# vehicle_control_module_0_1_0.net
KiCad netlist of a schematic drawn in EAGLE
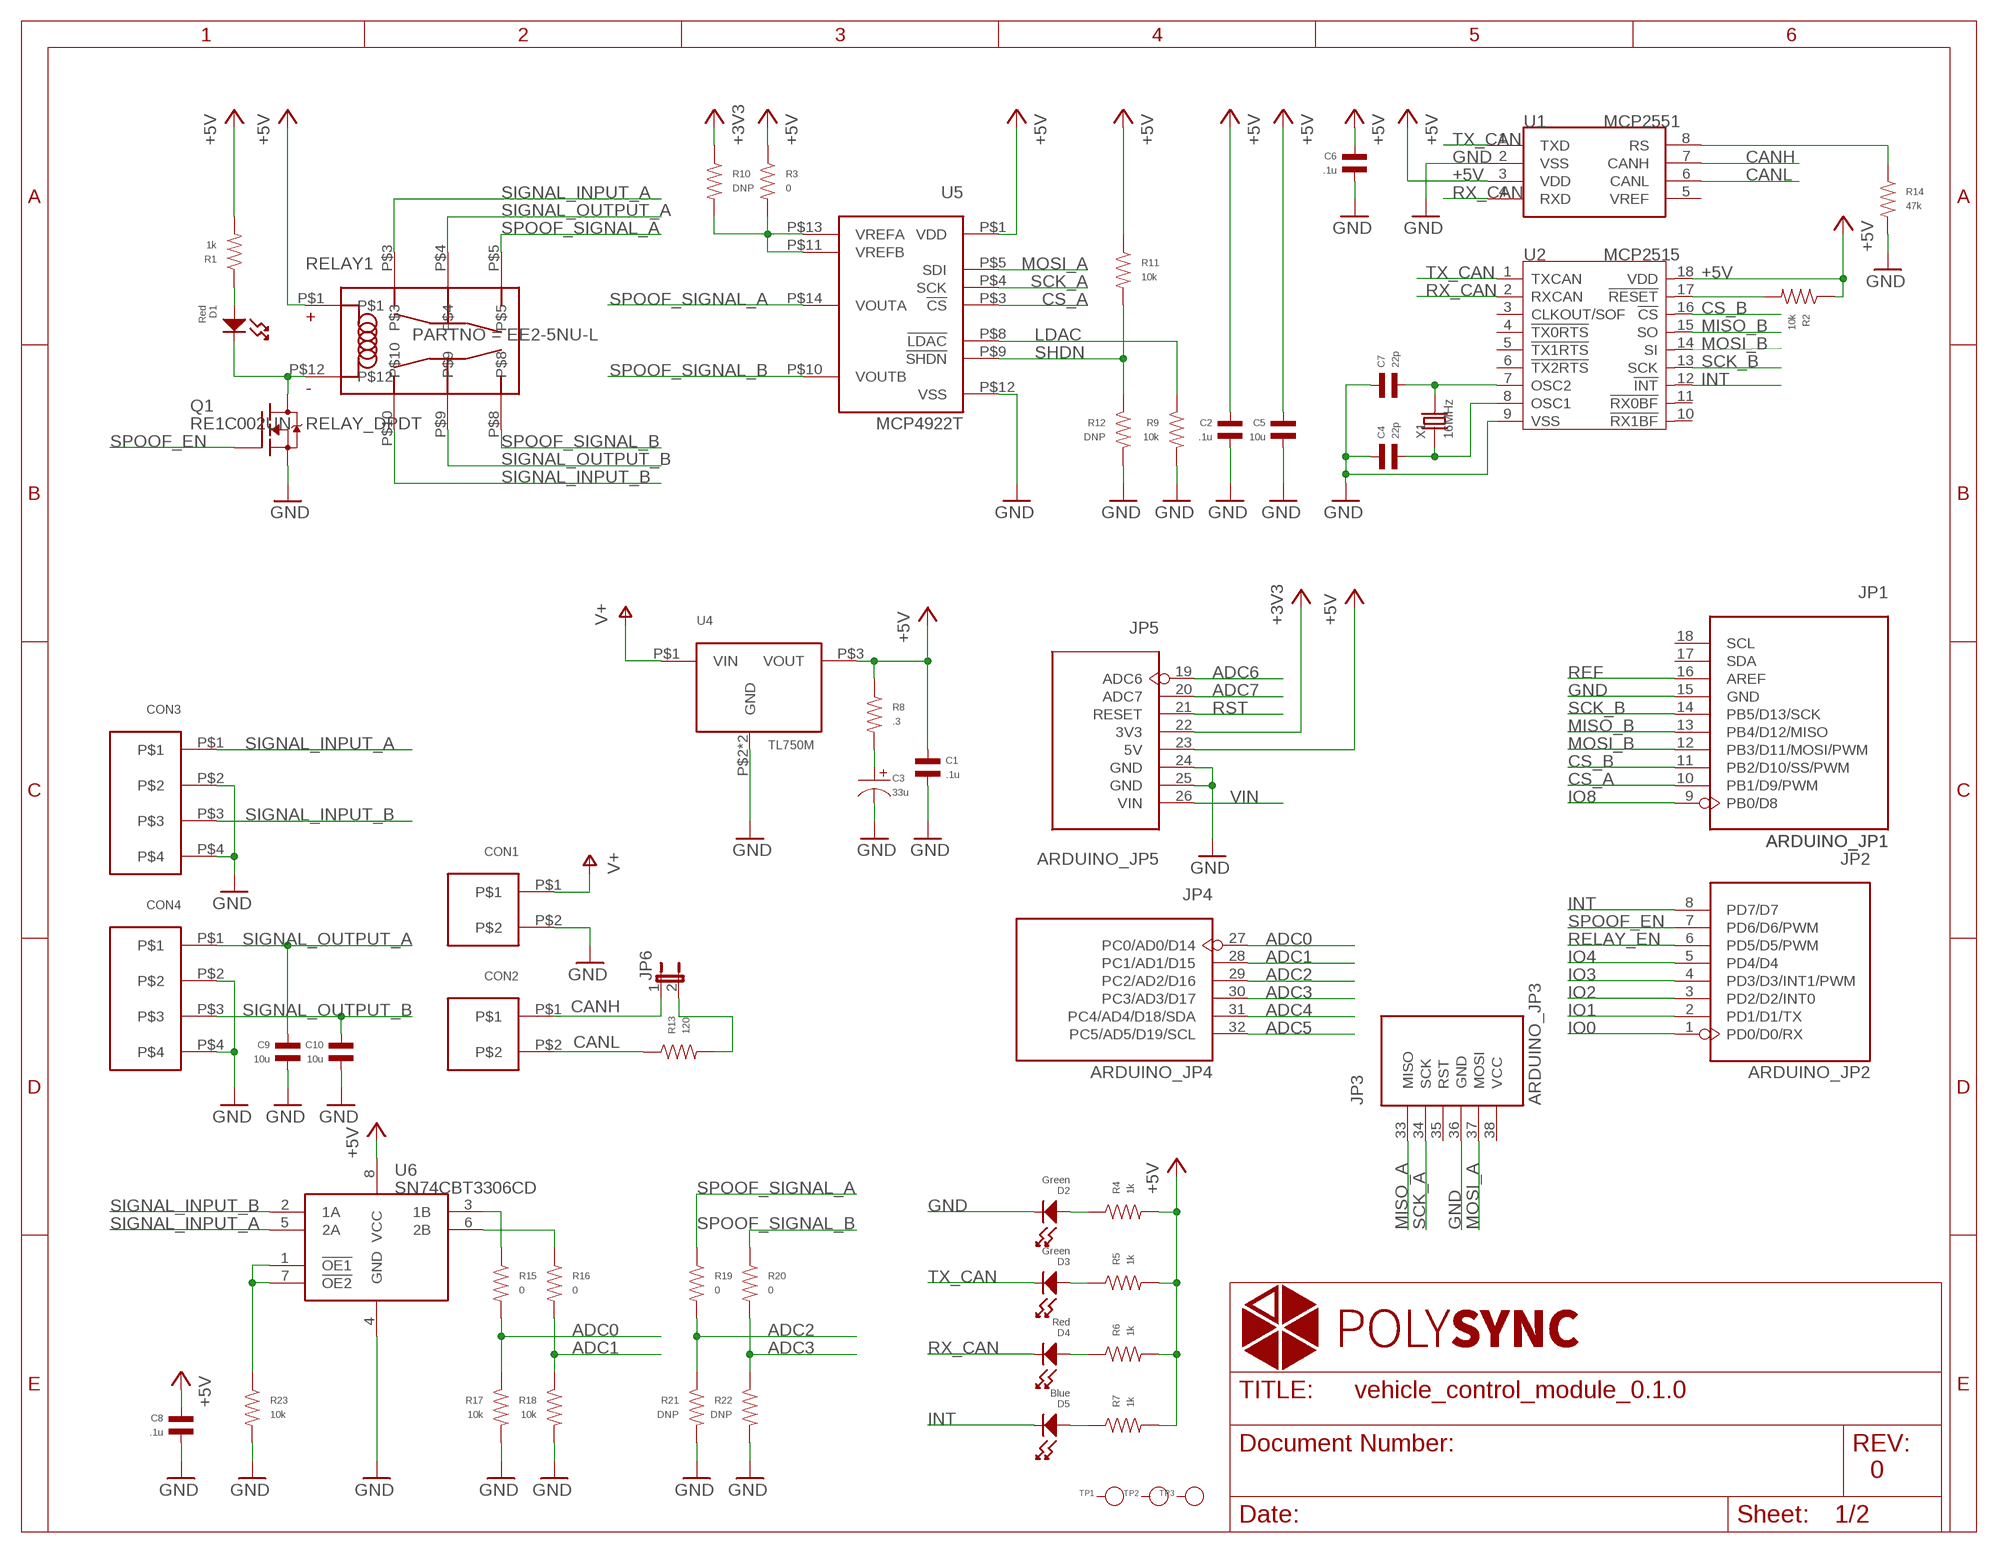
[diagram p0: schematic, sheet 1]
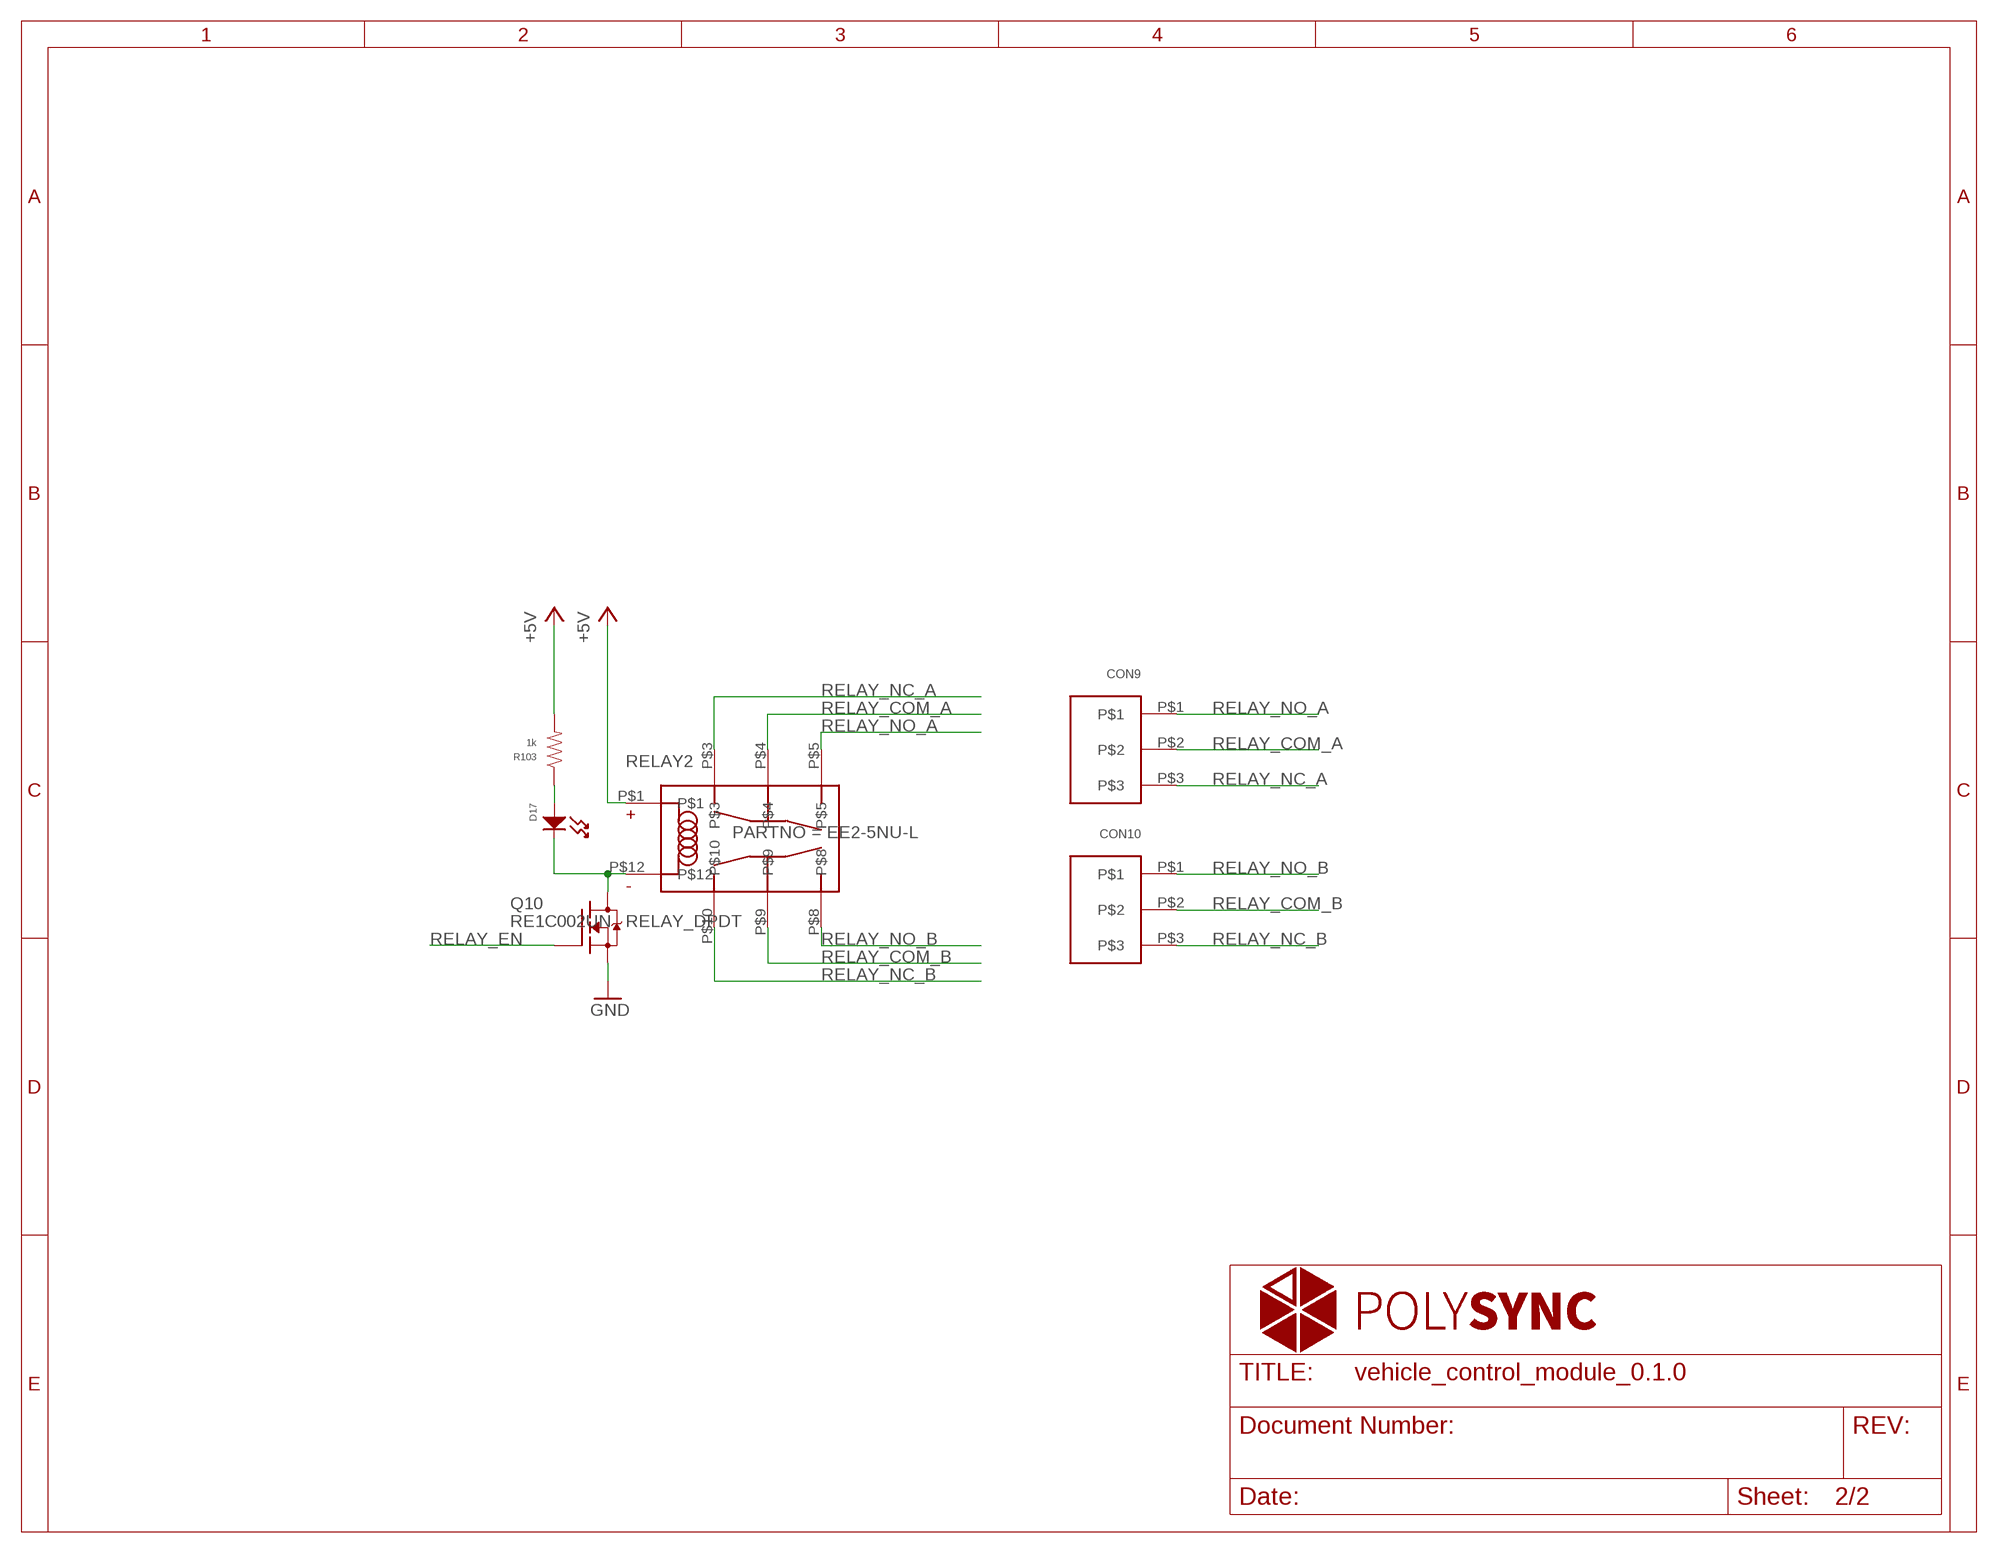
[diagram p1: schematic, sheet 2]

(export (version "E")
  (design (tool "Eeschema 10.0.6"))
  (components
    (comp (ref "CON9")
      (value "CON3")
      (footprint "eagle-import:PHOENIX_3_45")
      (libsource (lib "eagle-import") (part "CON3"))
    )
    (comp (ref "CON10")
      (value "CON3")
      (footprint "eagle-import:PHOENIX_3_45")
      (libsource (lib "eagle-import") (part "CON3"))
    )
    (comp (ref "D17")
      (value "LED_SINGLE-0603")
      (footprint "eagle-import:LED0603")
      (fields (field (name "HOUSEPART") "NO"))
      (libsource (lib "eagle-import") (part "LED_SINGLE-0603"))
    )
    (comp (ref "Q10")
      (value "RE1C002UN")
      (footprint "eagle-import:EMT3F")
      (libsource (lib "eagle-import") (part "RE1C002UN"))
    )
    (comp (ref "R103")
      (value "1k")
      (footprint "eagle-import:R0402")
      (libsource (lib "eagle-import") (part "RESISTOR_0402"))
    )
    (comp (ref "RELAY2")
      (value "RELAY_DPDT")
      (footprint "eagle-import:KEMET_EE2")
      (fields (field (name "PARTNO") "EE2-5NU-L"))
      (libsource (lib "eagle-import") (part "RELAY_DPDT"))
    )
    (comp (ref "C1")
      (value ".1u")
      (footprint "eagle-import:C0402")
      (libsource (lib "eagle-import") (part "CAPACITOR_NP_0402"))
    )
    (comp (ref "C2")
      (value ".1u")
      (footprint "eagle-import:C0402")
      (libsource (lib "eagle-import") (part "CAPACITOR_NP_0402"))
    )
    (comp (ref "C3")
      (value "33u")
      (footprint "eagle-import:CP1206")
      (libsource (lib "eagle-import") (part "CAPACITOR_P"))
    )
    (comp (ref "C4")
      (value "22p")
      (footprint "eagle-import:C0402")
      (libsource (lib "eagle-import") (part "CAPACITOR_NP_0402"))
    )
    (comp (ref "C5")
      (value "10u")
      (footprint "eagle-import:C0805")
      (libsource (lib "eagle-import") (part "CAPACITOR_NP_0805"))
    )
    (comp (ref "C6")
      (value ".1u")
      (footprint "eagle-import:C0402")
      (libsource (lib "eagle-import") (part "CAPACITOR_NP_0402"))
    )
    (comp (ref "C7")
      (value "22p")
      (footprint "eagle-import:C0402")
      (libsource (lib "eagle-import") (part "CAPACITOR_NP_0402"))
    )
    (comp (ref "C8")
      (value ".1u")
      (footprint "eagle-import:C0402")
      (libsource (lib "eagle-import") (part "CAPACITOR_NP_0402"))
    )
    (comp (ref "C9")
      (value "10u")
      (footprint "eagle-import:C0805")
      (libsource (lib "eagle-import") (part "CAPACITOR_NP_0805"))
    )
    (comp (ref "C10")
      (value "10u")
      (footprint "eagle-import:C0805")
      (libsource (lib "eagle-import") (part "CAPACITOR_NP_0805"))
    )
    (comp (ref "CON1")
      (value "CON23.5MM")
      (footprint "eagle-import:PHOENIX_2_45")
      (libsource (lib "eagle-import") (part "CON23.5MM"))
    )
    (comp (ref "CON2")
      (value "CON23.5MM")
      (footprint "eagle-import:PHOENIX_2_45")
      (libsource (lib "eagle-import") (part "CON23.5MM"))
    )
    (comp (ref "CON3")
      (value "CON4")
      (footprint "eagle-import:PHOENIX_4_45")
      (libsource (lib "eagle-import") (part "CON4"))
    )
    (comp (ref "CON4")
      (value "CON4")
      (footprint "eagle-import:PHOENIX_4_45")
      (libsource (lib "eagle-import") (part "CON4"))
    )
    (comp (ref "D1")
      (value "Red")
      (footprint "eagle-import:LED0603")
      (fields (field (name "HOUSEPART") "NO"))
      (libsource (lib "eagle-import") (part "LED_SINGLE-0603"))
    )
    (comp (ref "D2")
      (value "Green")
      (footprint "eagle-import:LED0603")
      (fields (field (name "HOUSEPART") "NO"))
      (libsource (lib "eagle-import") (part "LED_SINGLE-0603"))
    )
    (comp (ref "D3")
      (value "Green")
      (footprint "eagle-import:LED0603")
      (fields (field (name "HOUSEPART") "NO"))
      (libsource (lib "eagle-import") (part "LED_SINGLE-0603"))
    )
    (comp (ref "D4")
      (value "Red")
      (footprint "eagle-import:LED0603")
      (fields (field (name "HOUSEPART") "NO"))
      (libsource (lib "eagle-import") (part "LED_SINGLE-0603"))
    )
    (comp (ref "D5")
      (value "Blue")
      (footprint "eagle-import:LED0603")
      (fields (field (name "HOUSEPART") "NO"))
      (libsource (lib "eagle-import") (part "LED_SINGLE-0603"))
    )
    (comp (ref "JP1")
      (value "ARDUINO_JP1")
      (footprint "eagle-import:ARDUINO_JP1")
      (libsource (lib "eagle-import") (part "ARDUINO_JP1"))
    )
    (comp (ref "JP2")
      (value "ARDUINO_JP2")
      (footprint "eagle-import:ARDUINO_JP2")
      (libsource (lib "eagle-import") (part "ARDUINO_JP2"))
    )
    (comp (ref "JP3")
      (value "ARDUINO_JP3")
      (footprint "eagle-import:ARDUINO_JP3")
      (libsource (lib "eagle-import") (part "ARDUINO_JP3"))
    )
    (comp (ref "JP4")
      (value "ARDUINO_JP4")
      (footprint "eagle-import:ARDUINO_JP4")
      (libsource (lib "eagle-import") (part "ARDUINO_JP4"))
    )
    (comp (ref "JP5")
      (value "ARDUINO_JP5")
      (footprint "eagle-import:ARDUINO_JP5")
      (libsource (lib "eagle-import") (part "ARDUINO_JP5"))
    )
    (comp (ref "JP6")
      (value "JP1E")
      (footprint "eagle-import:JP1")
      (libsource (lib "eagle-import") (part "JP1E"))
    )
    (comp (ref "Q1")
      (value "RE1C002UN")
      (footprint "eagle-import:EMT3F")
      (libsource (lib "eagle-import") (part "RE1C002UN"))
    )
    (comp (ref "R1")
      (value "1k")
      (footprint "eagle-import:R0402")
      (libsource (lib "eagle-import") (part "RESISTOR_0402"))
    )
    (comp (ref "R2")
      (value "10k")
      (footprint "eagle-import:R0402")
      (libsource (lib "eagle-import") (part "RESISTOR_0402"))
    )
    (comp (ref "R3")
      (value "0")
      (footprint "eagle-import:R0402")
      (libsource (lib "eagle-import") (part "RESISTOR_0402"))
    )
    (comp (ref "R4")
      (value "1k")
      (footprint "eagle-import:R0402")
      (libsource (lib "eagle-import") (part "RESISTOR_0402"))
    )
    (comp (ref "R5")
      (value "1k")
      (footprint "eagle-import:R0402")
      (libsource (lib "eagle-import") (part "RESISTOR_0402"))
    )
    (comp (ref "R6")
      (value "1k")
      (footprint "eagle-import:R0402")
      (libsource (lib "eagle-import") (part "RESISTOR_0402"))
    )
    (comp (ref "R7")
      (value "1k")
      (footprint "eagle-import:R0402")
      (libsource (lib "eagle-import") (part "RESISTOR_0402"))
    )
    (comp (ref "R8")
      (value ".3")
      (footprint "eagle-import:R0402")
      (libsource (lib "eagle-import") (part "RESISTOR_0402"))
    )
    (comp (ref "R9")
      (value "10k")
      (footprint "eagle-import:R0402")
      (libsource (lib "eagle-import") (part "RESISTOR_0402"))
    )
    (comp (ref "R10")
      (value "DNP")
      (footprint "eagle-import:R0402")
      (libsource (lib "eagle-import") (part "RESISTOR_0402"))
    )
    (comp (ref "R11")
      (value "10k")
      (footprint "eagle-import:R0402")
      (libsource (lib "eagle-import") (part "RESISTOR_0402"))
    )
    (comp (ref "R12")
      (value "DNP")
      (footprint "eagle-import:R0402")
      (libsource (lib "eagle-import") (part "RESISTOR_0402"))
    )
    (comp (ref "R13")
      (value "120")
      (footprint "eagle-import:R0402")
      (libsource (lib "eagle-import") (part "RESISTOR_0402"))
    )
    (comp (ref "R14")
      (value "47k")
      (footprint "eagle-import:R0402")
      (libsource (lib "eagle-import") (part "RESISTOR_0402"))
    )
    (comp (ref "R15")
      (value "0")
      (footprint "eagle-import:R0402")
      (libsource (lib "eagle-import") (part "RESISTOR_0402"))
    )
    (comp (ref "R16")
      (value "0")
      (footprint "eagle-import:R0402")
      (libsource (lib "eagle-import") (part "RESISTOR_0402"))
    )
    (comp (ref "R17")
      (value "10k")
      (footprint "eagle-import:R0402")
      (libsource (lib "eagle-import") (part "RESISTOR_0402"))
    )
    (comp (ref "R18")
      (value "10k")
      (footprint "eagle-import:R0402")
      (libsource (lib "eagle-import") (part "RESISTOR_0402"))
    )
    (comp (ref "R19")
      (value "0")
      (footprint "eagle-import:R0402")
      (libsource (lib "eagle-import") (part "RESISTOR_0402"))
    )
    (comp (ref "R20")
      (value "0")
      (footprint "eagle-import:R0402")
      (libsource (lib "eagle-import") (part "RESISTOR_0402"))
    )
    (comp (ref "R21")
      (value "DNP")
      (footprint "eagle-import:R0402")
      (libsource (lib "eagle-import") (part "RESISTOR_0402"))
    )
    (comp (ref "R22")
      (value "DNP")
      (footprint "eagle-import:R0402")
      (libsource (lib "eagle-import") (part "RESISTOR_0402"))
    )
    (comp (ref "R23")
      (value "10k")
      (footprint "eagle-import:R0402")
      (libsource (lib "eagle-import") (part "RESISTOR_0402"))
    )
    (comp (ref "RELAY1")
      (value "RELAY_DPDT")
      (footprint "eagle-import:KEMET_EE2")
      (fields (field (name "PARTNO") "EE2-5NU-L"))
      (libsource (lib "eagle-import") (part "RELAY_DPDT"))
    )
    (comp (ref "TP1")
      (value "PAD-TEST-POINT'4545'")
      (footprint "eagle-import:TP_4545")
      (fields (field (name "PARTNO") "DNP"))
      (libsource (lib "eagle-import") (part "PAD-TEST-POINT'4545'"))
    )
    (comp (ref "TP2")
      (value "PAD-TEST-POINT'4545'")
      (footprint "eagle-import:TP_4545")
      (fields (field (name "PARTNO") "DNP"))
      (libsource (lib "eagle-import") (part "PAD-TEST-POINT'4545'"))
    )
    (comp (ref "TP3")
      (value "PAD-TEST-POINT'4545'")
      (footprint "eagle-import:TP_4545")
      (fields (field (name "PARTNO") "DNP"))
      (libsource (lib "eagle-import") (part "PAD-TEST-POINT'4545'"))
    )
    (comp (ref "U1")
      (value "MCP2551")
      (footprint "eagle-import:SOIC8-6.0")
      (libsource (lib "eagle-import") (part "MCP2551-SOIC8"))
    )
    (comp (ref "U2")
      (value "MCP2515")
      (footprint "eagle-import:SOIC18")
      (libsource (lib "eagle-import") (part "MCP2515-SOIC18"))
    )
    (comp (ref "U4")
      (value "TL750M")
      (footprint "eagle-import:TO-263")
      (libsource (lib "eagle-import") (part "TL750M"))
    )
    (comp (ref "U5")
      (value "MCP4922T")
      (footprint "eagle-import:TSSOP-14")
      (libsource (lib "eagle-import") (part "MCP4922T"))
    )
    (comp (ref "U6")
      (value "SN74CBT3306CD")
      (footprint "eagle-import:SOIC-8")
      (libsource (lib "eagle-import") (part "SN74CBT3306CD"))
    )
    (comp (ref "X1")
      (value "16MHz")
      (footprint "eagle-import:HC49UP")
      (libsource (lib "eagle-import") (part "CRYSTAL-HC49UP"))
    )
  )
  (nets
    (net (code "1") (name "+3V3") (class "Default")
      (node (ref "JP5") (pin "22") (pinfunction "3V3_22") (pintype "bidirectional"))
      (node (ref "R10") (pin "P$1") (pinfunction "P$1_P$1") (pintype "passive"))
    )
    (net (code "2") (name "+5V") (class "Default")
      (node (ref "C1") (pin "P$1") (pinfunction "P$1_P$1") (pintype "passive"))
      (node (ref "C2") (pin "P$1") (pinfunction "P$1_P$1") (pintype "passive"))
      (node (ref "C5") (pin "P$1") (pinfunction "P$1_P$1") (pintype "passive"))
      (node (ref "C6") (pin "P$1") (pinfunction "P$1_P$1") (pintype "passive"))
      (node (ref "C8") (pin "P$1") (pinfunction "P$1_P$1") (pintype "passive"))
      (node (ref "JP5") (pin "23") (pinfunction "5V_23") (pintype "bidirectional"))
      (node (ref "R1") (pin "P$2") (pinfunction "P$2_P$2") (pintype "passive"))
      (node (ref "R103") (pin "P$2") (pinfunction "P$2_P$2") (pintype "passive"))
      (node (ref "R11") (pin "P$1") (pinfunction "P$1_P$1") (pintype "passive"))
      (node (ref "R2") (pin "P$1") (pinfunction "P$1_P$1") (pintype "passive"))
      (node (ref "R3") (pin "P$1") (pinfunction "P$1_P$1") (pintype "passive"))
      (node (ref "R4") (pin "P$2") (pinfunction "P$2_P$2") (pintype "passive"))
      (node (ref "R5") (pin "P$2") (pinfunction "P$2_P$2") (pintype "passive"))
      (node (ref "R6") (pin "P$2") (pinfunction "P$2_P$2") (pintype "passive"))
      (node (ref "R7") (pin "P$2") (pinfunction "P$2_P$2") (pintype "passive"))
      (node (ref "R8") (pin "P$1") (pinfunction "P$1_P$1") (pintype "passive"))
      (node (ref "RELAY1") (pin "P$1") (pinfunction "P$1_P$1") (pintype "bidirectional"))
      (node (ref "RELAY2") (pin "P$1") (pinfunction "P$1_P$1") (pintype "bidirectional"))
      (node (ref "U1") (pin "3") (pinfunction "VDD_3") (pintype "bidirectional"))
      (node (ref "U2") (pin "18") (pinfunction "VDD_18") (pintype "power_in"))
      (node (ref "U4") (pin "P$3") (pinfunction "VOUT_P$3") (pintype "bidirectional"))
      (node (ref "U5") (pin "P$1") (pinfunction "VDD_P$1") (pintype "bidirectional"))
      (node (ref "U6") (pin "8") (pinfunction "VCC_8") (pintype "bidirectional"))
    )
    (net (code "3") (name "ADC0") (class "Default")
      (node (ref "JP4") (pin "27") (pinfunction "PC0/AD0/D14_27") (pintype "bidirectional"))
      (node (ref "R15") (pin "P$2") (pinfunction "P$2_P$2") (pintype "passive"))
      (node (ref "R17") (pin "P$1") (pinfunction "P$1_P$1") (pintype "passive"))
    )
    (net (code "4") (name "ADC1") (class "Default")
      (node (ref "JP4") (pin "28") (pinfunction "PC1/AD1/D15_28") (pintype "bidirectional"))
      (node (ref "R16") (pin "P$2") (pinfunction "P$2_P$2") (pintype "passive"))
      (node (ref "R18") (pin "P$1") (pinfunction "P$1_P$1") (pintype "passive"))
    )
    (net (code "5") (name "ADC2") (class "Default")
      (node (ref "JP4") (pin "29") (pinfunction "PC2/AD2/D16_29") (pintype "bidirectional"))
      (node (ref "R19") (pin "P$2") (pinfunction "P$2_P$2") (pintype "passive"))
      (node (ref "R21") (pin "P$1") (pinfunction "P$1_P$1") (pintype "passive"))
    )
    (net (code "6") (name "ADC3") (class "Default")
      (node (ref "JP4") (pin "30") (pinfunction "PC3/AD3/D17_30") (pintype "bidirectional"))
      (node (ref "R20") (pin "P$2") (pinfunction "P$2_P$2") (pintype "passive"))
      (node (ref "R22") (pin "P$1") (pinfunction "P$1_P$1") (pintype "passive"))
    )
    (net (code "7") (name "ADC4") (class "Default")
      (node (ref "JP4") (pin "31") (pinfunction "PC4/AD4/D18/SDA_31") (pintype "bidirectional"))
    )
    (net (code "8") (name "ADC5") (class "Default")
      (node (ref "JP4") (pin "32") (pinfunction "PC5/AD5/D19/SCL_32") (pintype "bidirectional"))
    )
    (net (code "9") (name "ADC6") (class "Default")
      (node (ref "JP5") (pin "19") (pinfunction "ADC6_19") (pintype "bidirectional"))
    )
    (net (code "10") (name "ADC7") (class "Default")
      (node (ref "JP5") (pin "20") (pinfunction "ADC7_20") (pintype "bidirectional"))
    )
    (net (code "11") (name "CANH") (class "Default")
      (node (ref "CON2") (pin "P$1") (pinfunction "P$1_P$1") (pintype "bidirectional"))
      (node (ref "JP6") (pin "1") (pinfunction "1_1") (pintype "passive"))
      (node (ref "U1") (pin "7") (pinfunction "CANH_7") (pintype "bidirectional"))
    )
    (net (code "12") (name "CANL") (class "Default")
      (node (ref "CON2") (pin "P$2") (pinfunction "P$2_P$2") (pintype "bidirectional"))
      (node (ref "R13") (pin "P$1") (pinfunction "P$1_P$1") (pintype "passive"))
      (node (ref "U1") (pin "6") (pinfunction "CANL_6") (pintype "bidirectional"))
    )
    (net (code "13") (name "CS_A") (class "Default")
      (node (ref "JP1") (pin "10") (pinfunction "PB1/D9/PWM_10") (pintype "bidirectional"))
      (node (ref "U5") (pin "P$3") (pinfunction "~{CS}_P$3") (pintype "bidirectional"))
    )
    (net (code "14") (name "CS_B") (class "Default")
      (node (ref "JP1") (pin "11") (pinfunction "PB2/D10/SS/PWM_11") (pintype "bidirectional"))
      (node (ref "U2") (pin "16") (pinfunction "~{CS}_16") (pintype "input"))
    )
    (net (code "15") (name "GND") (class "Default")
      (node (ref "C1") (pin "P$2") (pinfunction "P$2_P$2") (pintype "passive"))
      (node (ref "C10") (pin "P$2") (pinfunction "P$2_P$2") (pintype "passive"))
      (node (ref "C2") (pin "P$2") (pinfunction "P$2_P$2") (pintype "passive"))
      (node (ref "C3") (pin "P$2") (pinfunction "P$2_P$2") (pintype "passive"))
      (node (ref "C4") (pin "P$1") (pinfunction "P$1_P$1") (pintype "passive"))
      (node (ref "C5") (pin "P$2") (pinfunction "P$2_P$2") (pintype "passive"))
      (node (ref "C6") (pin "P$2") (pinfunction "P$2_P$2") (pintype "passive"))
      (node (ref "C7") (pin "P$1") (pinfunction "P$1_P$1") (pintype "passive"))
      (node (ref "C8") (pin "P$2") (pinfunction "P$2_P$2") (pintype "passive"))
      (node (ref "C9") (pin "P$2") (pinfunction "P$2_P$2") (pintype "passive"))
      (node (ref "CON1") (pin "P$2") (pinfunction "P$2_P$2") (pintype "bidirectional"))
      (node (ref "CON3") (pin "P$2") (pinfunction "P$2_P$2") (pintype "bidirectional"))
      (node (ref "CON3") (pin "P$4") (pinfunction "P$4_P$4") (pintype "bidirectional"))
      (node (ref "CON4") (pin "P$2") (pinfunction "P$2_P$2") (pintype "bidirectional"))
      (node (ref "CON4") (pin "P$4") (pinfunction "P$4_P$4") (pintype "bidirectional"))
      (node (ref "D2") (pin "CATHODE") (pinfunction "CATHODE_CATHODE") (pintype "power_in"))
      (node (ref "JP1") (pin "15") (pinfunction "GND_15") (pintype "bidirectional"))
      (node (ref "JP3") (pin "36") (pinfunction "GND_36") (pintype "bidirectional"))
      (node (ref "JP5") (pin "24") (pinfunction "GND_24") (pintype "bidirectional"))
      (node (ref "JP5") (pin "25") (pinfunction "GND_25") (pintype "bidirectional"))
      (node (ref "Q1") (pin "P$2") (pinfunction "S_P$2") (pintype "passive"))
      (node (ref "Q10") (pin "P$2") (pinfunction "S_P$2") (pintype "passive"))
      (node (ref "R12") (pin "P$2") (pinfunction "P$2_P$2") (pintype "passive"))
      (node (ref "R14") (pin "P$2") (pinfunction "P$2_P$2") (pintype "passive"))
      (node (ref "R17") (pin "P$2") (pinfunction "P$2_P$2") (pintype "passive"))
      (node (ref "R18") (pin "P$2") (pinfunction "P$2_P$2") (pintype "passive"))
      (node (ref "R21") (pin "P$2") (pinfunction "P$2_P$2") (pintype "passive"))
      (node (ref "R22") (pin "P$2") (pinfunction "P$2_P$2") (pintype "passive"))
      (node (ref "R23") (pin "P$2") (pinfunction "P$2_P$2") (pintype "passive"))
      (node (ref "R9") (pin "P$2") (pinfunction "P$2_P$2") (pintype "passive"))
      (node (ref "U1") (pin "2") (pinfunction "VSS_2") (pintype "bidirectional"))
      (node (ref "U2") (pin "9") (pinfunction "VSS_9") (pintype "power_in"))
      (node (ref "U4") (pin "P$2") (pinfunction "GND_P$2") (pintype "bidirectional"))
      (node (ref "U4") (pin "P$4") (pinfunction "GND_P$4") (pintype "bidirectional"))
      (node (ref "U5") (pin "P$12") (pinfunction "VSS_P$12") (pintype "bidirectional"))
      (node (ref "U6") (pin "4") (pinfunction "GND_4") (pintype "bidirectional"))
    )
    (net (code "16") (name "INT") (class "Default")
      (node (ref "D5") (pin "CATHODE") (pinfunction "CATHODE_CATHODE") (pintype "power_in"))
      (node (ref "JP2") (pin "8") (pinfunction "PD7/D7_8") (pintype "bidirectional"))
      (node (ref "U2") (pin "12") (pinfunction "~{INT}_12") (pintype "output"))
    )
    (net (code "17") (name "IO0") (class "Default")
      (node (ref "JP2") (pin "1") (pinfunction "PD0/D0/RX_1") (pintype "bidirectional"))
    )
    (net (code "18") (name "IO1") (class "Default")
      (node (ref "JP2") (pin "2") (pinfunction "PD1/D1/TX_2") (pintype "bidirectional"))
    )
    (net (code "19") (name "IO2") (class "Default")
      (node (ref "JP2") (pin "3") (pinfunction "PD2/D2/INT0_3") (pintype "bidirectional"))
    )
    (net (code "20") (name "IO3") (class "Default")
      (node (ref "JP2") (pin "4") (pinfunction "PD3/D3/INT1/PWM_4") (pintype "bidirectional"))
    )
    (net (code "21") (name "IO4") (class "Default")
      (node (ref "JP2") (pin "5") (pinfunction "PD4/D4_5") (pintype "bidirectional"))
    )
    (net (code "22") (name "IO8") (class "Default")
      (node (ref "JP1") (pin "9") (pinfunction "PB0/D8_9") (pintype "bidirectional"))
    )
    (net (code "23") (name "LDAC") (class "Default")
      (node (ref "R9") (pin "P$1") (pinfunction "P$1_P$1") (pintype "passive"))
      (node (ref "U5") (pin "P$8") (pinfunction "~{LDAC}_P$8") (pintype "bidirectional"))
    )
    (net (code "24") (name "MISO_A") (class "Default")
      (node (ref "JP3") (pin "33") (pinfunction "MISO_33") (pintype "bidirectional"))
    )
    (net (code "25") (name "MISO_B") (class "Default")
      (node (ref "JP1") (pin "13") (pinfunction "PB4/D12/MISO_13") (pintype "bidirectional"))
      (node (ref "U2") (pin "15") (pinfunction "SO_15") (pintype "output"))
    )
    (net (code "26") (name "MOSI_A") (class "Default")
      (node (ref "JP3") (pin "37") (pinfunction "MOSI_37") (pintype "bidirectional"))
      (node (ref "U5") (pin "P$5") (pinfunction "SDI_P$5") (pintype "bidirectional"))
    )
    (net (code "27") (name "MOSI_B") (class "Default")
      (node (ref "JP1") (pin "12") (pinfunction "PB3/D11/MOSI/PWM_12") (pintype "bidirectional"))
      (node (ref "U2") (pin "14") (pinfunction "SI_14") (pintype "input"))
    )
    (net (code "28") (name "Net-(C3-PadP$1)") (class "Default")
      (node (ref "C3") (pin "P$1") (pinfunction "P$1_P$1") (pintype "passive"))
      (node (ref "R8") (pin "P$2") (pinfunction "P$2_P$2") (pintype "passive"))
    )
    (net (code "29") (name "Net-(D1-PadANODE)") (class "Default")
      (node (ref "D1") (pin "ANODE") (pinfunction "ANODE_ANODE") (pintype "power_in"))
      (node (ref "R1") (pin "P$1") (pinfunction "P$1_P$1") (pintype "passive"))
    )
    (net (code "30") (name "Net-(D2-PadANODE)") (class "Default")
      (node (ref "D2") (pin "ANODE") (pinfunction "ANODE_ANODE") (pintype "power_in"))
      (node (ref "R4") (pin "P$1") (pinfunction "P$1_P$1") (pintype "passive"))
    )
    (net (code "31") (name "Net-(D3-PadANODE)") (class "Default")
      (node (ref "D3") (pin "ANODE") (pinfunction "ANODE_ANODE") (pintype "power_in"))
      (node (ref "R5") (pin "P$1") (pinfunction "P$1_P$1") (pintype "passive"))
    )
    (net (code "32") (name "Net-(D4-PadANODE)") (class "Default")
      (node (ref "D4") (pin "ANODE") (pinfunction "ANODE_ANODE") (pintype "power_in"))
      (node (ref "R6") (pin "P$1") (pinfunction "P$1_P$1") (pintype "passive"))
    )
    (net (code "33") (name "Net-(D5-PadANODE)") (class "Default")
      (node (ref "D5") (pin "ANODE") (pinfunction "ANODE_ANODE") (pintype "power_in"))
      (node (ref "R7") (pin "P$1") (pinfunction "P$1_P$1") (pintype "passive"))
    )
    (net (code "34") (name "Net-(D17-PadANODE)") (class "Default")
      (node (ref "D17") (pin "ANODE") (pinfunction "ANODE_ANODE") (pintype "power_in"))
      (node (ref "R103") (pin "P$1") (pinfunction "P$1_P$1") (pintype "passive"))
    )
    (net (code "35") (name "Net-(JP6-Pad2)") (class "Default")
      (node (ref "JP6") (pin "2") (pinfunction "2_2") (pintype "passive"))
      (node (ref "R13") (pin "P$2") (pinfunction "P$2_P$2") (pintype "passive"))
    )
    (net (code "36") (name "Net-(Q1-D)") (class "Default")
      (node (ref "D1") (pin "CATHODE") (pinfunction "CATHODE_CATHODE") (pintype "power_in"))
      (node (ref "Q1") (pin "P$3") (pinfunction "D_P$3") (pintype "passive"))
      (node (ref "RELAY1") (pin "P$12") (pinfunction "P$12_P$12") (pintype "bidirectional"))
    )
    (net (code "37") (name "Net-(Q10-D)") (class "Default")
      (node (ref "D17") (pin "CATHODE") (pinfunction "CATHODE_CATHODE") (pintype "power_in"))
      (node (ref "Q10") (pin "P$3") (pinfunction "D_P$3") (pintype "passive"))
      (node (ref "RELAY2") (pin "P$12") (pinfunction "P$12_P$12") (pintype "bidirectional"))
    )
    (net (code "38") (name "Net-(U1-RS)") (class "Default")
      (node (ref "R14") (pin "P$1") (pinfunction "P$1_P$1") (pintype "passive"))
      (node (ref "U1") (pin "8") (pinfunction "RS_8") (pintype "bidirectional"))
    )
    (net (code "39") (name "Net-(U2-OSC1)") (class "Default")
      (node (ref "C4") (pin "P$2") (pinfunction "P$2_P$2") (pintype "passive"))
      (node (ref "U2") (pin "8") (pinfunction "OSC1_8") (pintype "input"))
      (node (ref "X1") (pin "1") (pinfunction "1_1") (pintype "passive"))
    )
    (net (code "40") (name "Net-(U2-OSC2)") (class "Default")
      (node (ref "C7") (pin "P$2") (pinfunction "P$2_P$2") (pintype "passive"))
      (node (ref "U2") (pin "7") (pinfunction "OSC2_7") (pintype "output"))
      (node (ref "X1") (pin "2") (pinfunction "2_2") (pintype "passive"))
    )
    (net (code "41") (name "Net-(U2-~{RESET})") (class "Default")
      (node (ref "R2") (pin "P$2") (pinfunction "P$2_P$2") (pintype "passive"))
      (node (ref "U2") (pin "17") (pinfunction "~{RESET}_17") (pintype "input"))
    )
    (net (code "42") (name "Net-(U5-VREFA)") (class "Default")
      (node (ref "R10") (pin "P$2") (pinfunction "P$2_P$2") (pintype "passive"))
      (node (ref "R3") (pin "P$2") (pinfunction "P$2_P$2") (pintype "passive"))
      (node (ref "U5") (pin "P$11") (pinfunction "VREFB_P$11") (pintype "bidirectional"))
      (node (ref "U5") (pin "P$13") (pinfunction "VREFA_P$13") (pintype "bidirectional"))
    )
    (net (code "43") (name "Net-(U6-1B)") (class "Default")
      (node (ref "R15") (pin "P$1") (pinfunction "P$1_P$1") (pintype "passive"))
      (node (ref "U6") (pin "3") (pinfunction "1B_3") (pintype "bidirectional"))
    )
    (net (code "44") (name "Net-(U6-2B)") (class "Default")
      (node (ref "R16") (pin "P$1") (pinfunction "P$1_P$1") (pintype "passive"))
      (node (ref "U6") (pin "6") (pinfunction "2B_6") (pintype "bidirectional"))
    )
    (net (code "45") (name "Net-(U6-~{OE1})") (class "Default")
      (node (ref "R23") (pin "P$1") (pinfunction "P$1_P$1") (pintype "passive"))
      (node (ref "U6") (pin "1") (pinfunction "~{OE1}_1") (pintype "bidirectional"))
      (node (ref "U6") (pin "7") (pinfunction "~{OE2}_7") (pintype "bidirectional"))
    )
    (net (code "46") (name "REF") (class "Default")
      (node (ref "JP1") (pin "16") (pinfunction "AREF_16") (pintype "bidirectional"))
    )
    (net (code "47") (name "RELAY_COM_A") (class "Default")
      (node (ref "CON9") (pin "P$2") (pinfunction "P$2_P$2") (pintype "bidirectional"))
      (node (ref "RELAY2") (pin "P$4") (pinfunction "P$4_P$4") (pintype "bidirectional"))
    )
    (net (code "48") (name "RELAY_COM_B") (class "Default")
      (node (ref "CON10") (pin "P$2") (pinfunction "P$2_P$2") (pintype "bidirectional"))
      (node (ref "RELAY2") (pin "P$9") (pinfunction "P$9_P$9") (pintype "bidirectional"))
    )
    (net (code "49") (name "RELAY_EN") (class "Default")
      (node (ref "JP2") (pin "6") (pinfunction "PD5/D5/PWM_6") (pintype "bidirectional"))
      (node (ref "Q10") (pin "P$1") (pinfunction "G_P$1") (pintype "passive"))
    )
    (net (code "50") (name "RELAY_NC_A") (class "Default")
      (node (ref "CON9") (pin "P$3") (pinfunction "P$3_P$3") (pintype "bidirectional"))
      (node (ref "RELAY2") (pin "P$3") (pinfunction "P$3_P$3") (pintype "bidirectional"))
    )
    (net (code "51") (name "RELAY_NC_B") (class "Default")
      (node (ref "CON10") (pin "P$3") (pinfunction "P$3_P$3") (pintype "bidirectional"))
      (node (ref "RELAY2") (pin "P$10") (pinfunction "P$10_P$10") (pintype "bidirectional"))
    )
    (net (code "52") (name "RELAY_NO_A") (class "Default")
      (node (ref "CON9") (pin "P$1") (pinfunction "P$1_P$1") (pintype "bidirectional"))
      (node (ref "RELAY2") (pin "P$5") (pinfunction "P$5_P$5") (pintype "bidirectional"))
    )
    (net (code "53") (name "RELAY_NO_B") (class "Default")
      (node (ref "CON10") (pin "P$1") (pinfunction "P$1_P$1") (pintype "bidirectional"))
      (node (ref "RELAY2") (pin "P$8") (pinfunction "P$8_P$8") (pintype "bidirectional"))
    )
    (net (code "54") (name "RST") (class "Default")
      (node (ref "JP5") (pin "21") (pinfunction "RESET_21") (pintype "bidirectional"))
    )
    (net (code "55") (name "RX_CAN") (class "Default")
      (node (ref "D4") (pin "CATHODE") (pinfunction "CATHODE_CATHODE") (pintype "power_in"))
      (node (ref "U1") (pin "4") (pinfunction "RXD_4") (pintype "bidirectional"))
      (node (ref "U2") (pin "2") (pinfunction "RXCAN_2") (pintype "input"))
    )
    (net (code "56") (name "SCK_A") (class "Default")
      (node (ref "JP3") (pin "34") (pinfunction "SCK_34") (pintype "bidirectional"))
      (node (ref "U5") (pin "P$4") (pinfunction "SCK_P$4") (pintype "bidirectional"))
    )
    (net (code "57") (name "SCK_B") (class "Default")
      (node (ref "JP1") (pin "14") (pinfunction "PB5/D13/SCK_14") (pintype "bidirectional"))
      (node (ref "U2") (pin "13") (pinfunction "SCK_13") (pintype "input"))
    )
    (net (code "58") (name "SHDN") (class "Default")
      (node (ref "R11") (pin "P$2") (pinfunction "P$2_P$2") (pintype "passive"))
      (node (ref "R12") (pin "P$1") (pinfunction "P$1_P$1") (pintype "passive"))
      (node (ref "U5") (pin "P$9") (pinfunction "~{SHDN}_P$9") (pintype "bidirectional"))
    )
    (net (code "59") (name "SIGNAL_INPUT_A") (class "Default")
      (node (ref "CON3") (pin "P$1") (pinfunction "P$1_P$1") (pintype "bidirectional"))
      (node (ref "RELAY1") (pin "P$3") (pinfunction "P$3_P$3") (pintype "bidirectional"))
      (node (ref "U6") (pin "5") (pinfunction "2A_5") (pintype "bidirectional"))
    )
    (net (code "60") (name "SIGNAL_INPUT_B") (class "Default")
      (node (ref "CON3") (pin "P$3") (pinfunction "P$3_P$3") (pintype "bidirectional"))
      (node (ref "RELAY1") (pin "P$10") (pinfunction "P$10_P$10") (pintype "bidirectional"))
      (node (ref "U6") (pin "2") (pinfunction "1A_2") (pintype "bidirectional"))
    )
    (net (code "61") (name "SIGNAL_OUTPUT_A") (class "Default")
      (node (ref "C9") (pin "P$1") (pinfunction "P$1_P$1") (pintype "passive"))
      (node (ref "CON4") (pin "P$1") (pinfunction "P$1_P$1") (pintype "bidirectional"))
      (node (ref "RELAY1") (pin "P$4") (pinfunction "P$4_P$4") (pintype "bidirectional"))
    )
    (net (code "62") (name "SIGNAL_OUTPUT_B") (class "Default")
      (node (ref "C10") (pin "P$1") (pinfunction "P$1_P$1") (pintype "passive"))
      (node (ref "CON4") (pin "P$3") (pinfunction "P$3_P$3") (pintype "bidirectional"))
      (node (ref "RELAY1") (pin "P$9") (pinfunction "P$9_P$9") (pintype "bidirectional"))
    )
    (net (code "63") (name "SPOOF_EN") (class "Default")
      (node (ref "JP2") (pin "7") (pinfunction "PD6/D6/PWM_7") (pintype "bidirectional"))
      (node (ref "Q1") (pin "P$1") (pinfunction "G_P$1") (pintype "passive"))
    )
    (net (code "64") (name "SPOOF_SIGNAL_A") (class "Default")
      (node (ref "R19") (pin "P$1") (pinfunction "P$1_P$1") (pintype "passive"))
      (node (ref "RELAY1") (pin "P$5") (pinfunction "P$5_P$5") (pintype "bidirectional"))
      (node (ref "U5") (pin "P$14") (pinfunction "VOUTA_P$14") (pintype "bidirectional"))
    )
    (net (code "65") (name "SPOOF_SIGNAL_B") (class "Default")
      (node (ref "R20") (pin "P$1") (pinfunction "P$1_P$1") (pintype "passive"))
      (node (ref "RELAY1") (pin "P$8") (pinfunction "P$8_P$8") (pintype "bidirectional"))
      (node (ref "U5") (pin "P$10") (pinfunction "VOUTB_P$10") (pintype "bidirectional"))
    )
    (net (code "66") (name "TX_CAN") (class "Default")
      (node (ref "D3") (pin "CATHODE") (pinfunction "CATHODE_CATHODE") (pintype "power_in"))
      (node (ref "U1") (pin "1") (pinfunction "TXD_1") (pintype "bidirectional"))
      (node (ref "U2") (pin "1") (pinfunction "TXCAN_1") (pintype "output"))
    )
    (net (code "67") (name "V+") (class "Default")
      (node (ref "CON1") (pin "P$1") (pinfunction "P$1_P$1") (pintype "bidirectional"))
      (node (ref "U4") (pin "P$1") (pinfunction "VIN_P$1") (pintype "bidirectional"))
    )
    (net (code "68") (name "VIN") (class "Default")
      (node (ref "JP5") (pin "26") (pinfunction "VIN_26") (pintype "bidirectional"))
    )
    (net (code "69") (name "unconnected-(JP1-SCL-Pad18)") (class "Default")
      (node (ref "JP1") (pin "18") (pinfunction "SCL_18") (pintype "bidirectional"))
    )
    (net (code "70") (name "unconnected-(JP1-SDA-Pad17)") (class "Default")
      (node (ref "JP1") (pin "17") (pinfunction "SDA_17") (pintype "bidirectional"))
    )
    (net (code "71") (name "unconnected-(JP3-RST-Pad35)") (class "Default")
      (node (ref "JP3") (pin "35") (pinfunction "RST_35") (pintype "bidirectional"))
    )
    (net (code "72") (name "unconnected-(JP3-VCC-Pad38)") (class "Default")
      (node (ref "JP3") (pin "38") (pinfunction "VCC_38") (pintype "bidirectional"))
    )
    (net (code "73") (name "unconnected-(TP1-PadT)") (class "Default")
      (node (ref "TP1") (pin "T") (pinfunction "T_T") (pintype "bidirectional"))
    )
    (net (code "74") (name "unconnected-(TP2-PadT)") (class "Default")
      (node (ref "TP2") (pin "T") (pinfunction "T_T") (pintype "bidirectional"))
    )
    (net (code "75") (name "unconnected-(TP3-PadT)") (class "Default")
      (node (ref "TP3") (pin "T") (pinfunction "T_T") (pintype "bidirectional"))
    )
    (net (code "76") (name "unconnected-(U1-VREF-Pad5)") (class "Default")
      (node (ref "U1") (pin "5") (pinfunction "VREF_5") (pintype "bidirectional"))
    )
    (net (code "77") (name "unconnected-(U2-CLKOUT{slash}SOF-Pad3)") (class "Default")
      (node (ref "U2") (pin "3") (pinfunction "CLKOUT/SOF_3") (pintype "output"))
    )
    (net (code "78") (name "unconnected-(U2-~{RX0BF}-Pad11)") (class "Default")
      (node (ref "U2") (pin "11") (pinfunction "~{RX0BF}_11") (pintype "output"))
    )
    (net (code "79") (name "unconnected-(U2-~{RX1BF}-Pad10)") (class "Default")
      (node (ref "U2") (pin "10") (pinfunction "~{RX1BF}_10") (pintype "output"))
    )
    (net (code "80") (name "unconnected-(U2-~{TX0RTS}-Pad4)") (class "Default")
      (node (ref "U2") (pin "4") (pinfunction "~{TX0RTS}_4") (pintype "input"))
    )
    (net (code "81") (name "unconnected-(U2-~{TX1RTS}-Pad5)") (class "Default")
      (node (ref "U2") (pin "5") (pinfunction "~{TX1RTS}_5") (pintype "input"))
    )
    (net (code "82") (name "unconnected-(U2-~{TX2RTS}-Pad6)") (class "Default")
      (node (ref "U2") (pin "6") (pinfunction "~{TX2RTS}_6") (pintype "input"))
    )
  )
)
